# 4_esp8266.net
KiCad netlist of a schematic drawn in Altium Designer
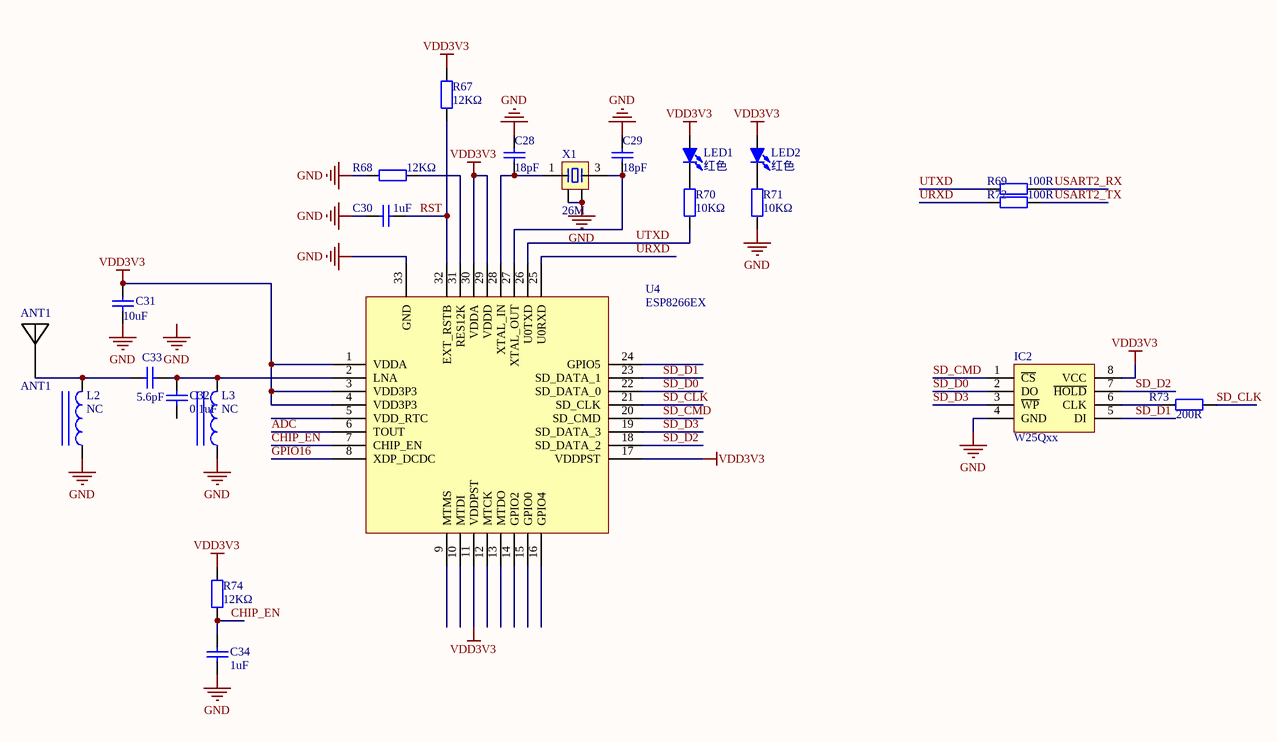
[diagram p0: 4_esp8266.SchDoc]

(export (version "E")
  (design (tool "Eeschema 10.0.6"))
  (components
    (comp (ref "ANT1")
      (value "ANT1")
      (footprint "WIFI-ANT")
      (description "PCB板载天线")
      (fields (field (name "版权归属") "源创客"))
      (libsource (lib "14.1 - 天线") (part "ANT1"))
    )
    (comp (ref "C28")
      (value "18pF")
      (footprint "LC-0603_C")
      (description "贴片电容")
      (libsource (lib "Miscellaneous Devices LC") (part "0603 1nF (102) 10% 50V"))
    )
    (comp (ref "C29")
      (value "18pF")
      (footprint "LC-0603_C")
      (description "贴片电容")
      (libsource (lib "Miscellaneous Devices LC") (part "0603 1nF (102) 10% 50V"))
    )
    (comp (ref "C30")
      (value "1uF")
      (footprint "LC-0603_C")
      (description "贴片电容")
      (libsource (lib "Miscellaneous Devices LC") (part "0603 1nF (102) 10% 50V"))
    )
    (comp (ref "C31")
      (value "10uF")
      (footprint "LC-0805_C")
      (description "贴片电容")
      (libsource (lib "Miscellaneous Devices LC") (part "0805 33pF (330) 5% 50V"))
    )
    (comp (ref "C32")
      (value "0.1uF")
      (footprint "LC-0603_C")
      (description "贴片电容")
      (libsource (lib "Miscellaneous Devices LC") (part "0603 1nF (102) 10% 50V"))
    )
    (comp (ref "C33")
      (value "5.6pF")
      (footprint "LC-0603_C")
      (description "贴片电容")
      (libsource (lib "Miscellaneous Devices LC") (part "0603 1nF (102) 10% 50V"))
    )
    (comp (ref "C34")
      (value "1uF")
      (footprint "LC-0603_C")
      (description "贴片电容")
      (libsource (lib "Miscellaneous Devices LC") (part "0603 1nF (102) 10% 50V"))
    )
    (comp (ref "IC2")
      (value "W25Qxx")
      (footprint "SOP8W_M")
      (description "外置Flash")
      (fields (field (name "版权归属") "源创客"))
      (libsource (lib "1.1   - IC芯片") (part "W25Qxx"))
    )
    (comp (ref "L2")
      (value "NC")
      (footprint "LC-0603_L")
      (description "贴片电感")
      (libsource (lib "Miscellaneous Devices LC") (part "0603 10uH 10%"))
    )
    (comp (ref "L3")
      (value "NC")
      (footprint "LC-0603_L")
      (description "贴片电感")
      (libsource (lib "Miscellaneous Devices LC") (part "0603 10uH 10%"))
    )
    (comp (ref "LED1")
      (value "红色")
      (footprint "LED 0603G")
      (description "贴片LED")
      (fields (field (name "版权归属") "源创客"))
      (libsource (lib "9.1   - LED") (part "LED-SMD"))
    )
    (comp (ref "LED2")
      (value "红色")
      (footprint "LED 0603G")
      (description "贴片LED")
      (fields (field (name "版权归属") "源创客"))
      (libsource (lib "9.1   - LED") (part "LED-SMD"))
    )
    (comp (ref "R67")
      (value "12KΩ")
      (footprint "LC-0603_R")
      (description "贴片电阻")
      (libsource (lib "Miscellaneous Devices LC") (part "0603 1.8KΩ (1801) 1%"))
    )
    (comp (ref "R68")
      (value "12KΩ")
      (footprint "LC-0603_R")
      (description "贴片电阻")
      (libsource (lib "") (part "0603 1.8KΩ (1801) 1%_1"))
    )
    (comp (ref "R69")
      (value "100R")
      (footprint "LC-0603_R")
      (description "贴片电阻")
      (fields (field (name "PUBLISHER") "Altium Limited"))
      (libsource (lib "liu_2016") (part "Res1"))
    )
    (comp (ref "R70")
      (value "10KΩ")
      (footprint "LC-0603_R")
      (description "贴片电阻")
      (libsource (lib "") (part "0603 1.8KΩ (1801) 1%_2"))
    )
    (comp (ref "R71")
      (value "10KΩ")
      (footprint "LC-0603_R")
      (description "贴片电阻")
      (libsource (lib "Miscellaneous Devices LC") (part "0603 1.8KΩ (1801) 1%"))
    )
    (comp (ref "R72")
      (value "100R")
      (footprint "LC-0603_R")
      (description "贴片电阻")
      (fields (field (name "PUBLISHER") "Altium Limited"))
      (libsource (lib "liu_2016") (part "Res1"))
    )
    (comp (ref "R73")
      (value "200R")
      (footprint "LC-0603_R")
      (description "贴片电阻")
      (libsource (lib "") (part "0603 1.8KΩ (1801) 1%_1"))
    )
    (comp (ref "R74")
      (value "12KΩ")
      (footprint "LC-0603_R")
      (description "贴片电阻")
      (libsource (lib "Miscellaneous Devices LC") (part "0603 1.8KΩ (1801) 1%"))
    )
    (comp (ref "U4")
      (value "ESP8266EX")
      (footprint "QFN32 5x5_M")
      (description "WIFI芯片")
      (libsource (lib "11.1 - 传感元件") (part "ESP8266EX"))
    )
    (comp (ref "X1")
      (value "26M")
      (footprint "OSC 2025-4P")
      (description "4脚无源晶振")
      (fields (field (name "版权归属") "源创客"))
      (libsource (lib "10.1 - 保险丝-晶振") (part "XTAL-4P"))
    )
  )
  (nets
    (net (code "1") (name "/ADC") (class "Default")
      (node (ref "U4") (pin "6") (pinfunction "TOUT_6") (pintype "passive"))
    )
    (net (code "2") (name "/CHIP_EN") (class "Default")
      (node (ref "C34") (pin "1") (pinfunction "1_1") (pintype "passive"))
      (node (ref "R74") (pin "1") (pinfunction "1_1") (pintype "passive"))
      (node (ref "U4") (pin "7") (pinfunction "CHIP_EN_7") (pintype "passive"))
    )
    (net (code "3") (name "/GPIO16") (class "Default")
      (node (ref "U4") (pin "8") (pinfunction "XDP_DCDC_8") (pintype "passive"))
    )
    (net (code "4") (name "/RST") (class "Default")
      (node (ref "C30") (pin "1") (pinfunction "1_1") (pintype "passive"))
      (node (ref "R67") (pin "1") (pinfunction "1_1") (pintype "passive"))
      (node (ref "U4") (pin "32") (pinfunction "EXT_RSTB_32") (pintype "passive"))
    )
    (net (code "5") (name "/SD_CLK") (class "Default")
      (node (ref "R73") (pin "1") (pinfunction "1_1") (pintype "passive"))
      (node (ref "U4") (pin "21") (pinfunction "SD_CLK_21") (pintype "passive"))
    )
    (net (code "6") (name "/SD_CMD") (class "Default")
      (node (ref "IC2") (pin "1") (pinfunction "~{CS}_1") (pintype "passive"))
      (node (ref "U4") (pin "20") (pinfunction "SD_CMD_20") (pintype "passive"))
    )
    (net (code "7") (name "/SD_D0") (class "Default")
      (node (ref "IC2") (pin "2") (pinfunction "DO_2") (pintype "passive"))
      (node (ref "U4") (pin "22") (pinfunction "SD_DATA_0_22") (pintype "passive"))
    )
    (net (code "8") (name "/SD_D1") (class "Default")
      (node (ref "IC2") (pin "5") (pinfunction "DI_5") (pintype "passive"))
      (node (ref "U4") (pin "23") (pinfunction "SD_DATA_1_23") (pintype "passive"))
    )
    (net (code "9") (name "/SD_D2") (class "Default")
      (node (ref "IC2") (pin "7") (pinfunction "~{HOLD}_7") (pintype "passive"))
      (node (ref "U4") (pin "18") (pinfunction "SD_DATA_2_18") (pintype "passive"))
    )
    (net (code "10") (name "/SD_D3") (class "Default")
      (node (ref "IC2") (pin "3") (pinfunction "~{WP}_3") (pintype "passive"))
      (node (ref "U4") (pin "19") (pinfunction "SD_DATA_3_19") (pintype "passive"))
    )
    (net (code "11") (name "/URXD") (class "Default")
      (node (ref "R72") (pin "2") (pinfunction "2_2") (pintype "passive"))
      (node (ref "U4") (pin "25") (pinfunction "U0RXD_25") (pintype "passive"))
    )
    (net (code "12") (name "/USART2_RX") (class "Default")
      (node (ref "R69") (pin "1") (pinfunction "1_1") (pintype "passive"))
    )
    (net (code "13") (name "/USART2_TX") (class "Default")
      (node (ref "R72") (pin "1") (pinfunction "1_1") (pintype "passive"))
    )
    (net (code "14") (name "/UTXD") (class "Default")
      (node (ref "R69") (pin "2") (pinfunction "2_2") (pintype "passive"))
      (node (ref "R70") (pin "2") (pinfunction "2_2") (pintype "passive"))
      (node (ref "U4") (pin "26") (pinfunction "U0TXD_26") (pintype "passive"))
    )
    (net (code "15") (name "GND") (class "Default")
      (node (ref "C28") (pin "1") (pinfunction "1_1") (pintype "passive"))
      (node (ref "C29") (pin "1") (pinfunction "1_1") (pintype "passive"))
      (node (ref "C30") (pin "2") (pinfunction "2_2") (pintype "passive"))
      (node (ref "C31") (pin "1") (pinfunction "1_1") (pintype "passive"))
      (node (ref "C34") (pin "2") (pinfunction "2_2") (pintype "passive"))
      (node (ref "IC2") (pin "4") (pinfunction "GND_4") (pintype "passive"))
      (node (ref "L2") (pin "1") (pinfunction "1_1") (pintype "passive"))
      (node (ref "L3") (pin "1") (pinfunction "1_1") (pintype "passive"))
      (node (ref "R68") (pin "2") (pinfunction "2_2") (pintype "passive"))
      (node (ref "R71") (pin "1") (pinfunction "1_1") (pintype "passive"))
      (node (ref "U4") (pin "33") (pinfunction "GND_33") (pintype "passive"))
      (node (ref "X1") (pin "2") (pinfunction "2_2") (pintype "passive"))
      (node (ref "X1") (pin "4") (pinfunction "4_4") (pintype "passive"))
    )
    (net (code "16") (name "Net-(ANT1-Pad1)") (class "Default")
      (node (ref "ANT1") (pin "1") (pinfunction "1_1") (pintype "passive"))
      (node (ref "C33") (pin "1") (pinfunction "1_1") (pintype "passive"))
      (node (ref "L2") (pin "2") (pinfunction "2_2") (pintype "passive"))
    )
    (net (code "17") (name "Net-(IC2-CLK)") (class "Default")
      (node (ref "IC2") (pin "6") (pinfunction "CLK_6") (pintype "passive"))
      (node (ref "R73") (pin "2") (pinfunction "2_2") (pintype "passive"))
    )
    (net (code "18") (name "Net-(LED1-K)") (class "Default")
      (node (ref "LED1") (pin "2") (pinfunction "K_2") (pintype "passive"))
      (node (ref "R70") (pin "1") (pinfunction "1_1") (pintype "passive"))
    )
    (net (code "19") (name "Net-(LED2-K)") (class "Default")
      (node (ref "LED2") (pin "2") (pinfunction "K_2") (pintype "passive"))
      (node (ref "R71") (pin "2") (pinfunction "2_2") (pintype "passive"))
    )
    (net (code "20") (name "Net-(U4-LNA)") (class "Default")
      (node (ref "C32") (pin "1") (pinfunction "1_1") (pintype "passive"))
      (node (ref "C33") (pin "2") (pinfunction "2_2") (pintype "passive"))
      (node (ref "L3") (pin "2") (pinfunction "2_2") (pintype "passive"))
      (node (ref "U4") (pin "2") (pinfunction "LNA_2") (pintype "passive"))
    )
    (net (code "21") (name "Net-(U4-RES12K)") (class "Default")
      (node (ref "R68") (pin "1") (pinfunction "1_1") (pintype "passive"))
      (node (ref "U4") (pin "31") (pinfunction "RES12K_31") (pintype "passive"))
    )
    (net (code "22") (name "Net-(U4-XTAL_IN)") (class "Default")
      (node (ref "C28") (pin "2") (pinfunction "2_2") (pintype "passive"))
      (node (ref "U4") (pin "28") (pinfunction "XTAL_IN_28") (pintype "passive"))
      (node (ref "X1") (pin "1") (pinfunction "1_1") (pintype "passive"))
    )
    (net (code "23") (name "Net-(U4-XTAL_OUT)") (class "Default")
      (node (ref "C29") (pin "2") (pinfunction "2_2") (pintype "passive"))
      (node (ref "U4") (pin "27") (pinfunction "XTAL_OUT_27") (pintype "passive"))
      (node (ref "X1") (pin "3") (pinfunction "3_3") (pintype "passive"))
    )
    (net (code "24") (name "VDD3V3") (class "Default")
      (node (ref "C31") (pin "2") (pinfunction "2_2") (pintype "passive"))
      (node (ref "IC2") (pin "8") (pinfunction "VCC_8") (pintype "passive"))
      (node (ref "LED1") (pin "1") (pinfunction "A_1") (pintype "passive"))
      (node (ref "LED2") (pin "1") (pinfunction "A_1") (pintype "passive"))
      (node (ref "R67") (pin "2") (pinfunction "2_2") (pintype "passive"))
      (node (ref "R74") (pin "2") (pinfunction "2_2") (pintype "passive"))
      (node (ref "U4") (pin "1") (pinfunction "VDDA_1") (pintype "passive"))
      (node (ref "U4") (pin "11") (pinfunction "VDDPST_11") (pintype "passive"))
      (node (ref "U4") (pin "17") (pinfunction "VDDPST_17") (pintype "passive"))
      (node (ref "U4") (pin "29") (pinfunction "VDDD_29") (pintype "passive"))
      (node (ref "U4") (pin "3") (pinfunction "VDD3P3_3") (pintype "passive"))
      (node (ref "U4") (pin "30") (pinfunction "VDDA_30") (pintype "passive"))
      (node (ref "U4") (pin "4") (pinfunction "VDD3P3_4") (pintype "passive"))
    )
    (net (code "25") (name "unconnected-(C32-Pad2)") (class "Default")
      (node (ref "C32") (pin "2") (pinfunction "2_2") (pintype "passive"))
    )
    (net (code "26") (name "unconnected-(U4-GPIO0-Pad15)") (class "Default")
      (node (ref "U4") (pin "15") (pinfunction "GPIO0_15") (pintype "passive"))
    )
    (net (code "27") (name "unconnected-(U4-GPIO2-Pad14)") (class "Default")
      (node (ref "U4") (pin "14") (pinfunction "GPIO2_14") (pintype "passive"))
    )
    (net (code "28") (name "unconnected-(U4-GPIO4-Pad16)") (class "Default")
      (node (ref "U4") (pin "16") (pinfunction "GPIO4_16") (pintype "passive"))
    )
    (net (code "29") (name "unconnected-(U4-GPIO5-Pad24)") (class "Default")
      (node (ref "U4") (pin "24") (pinfunction "GPIO5_24") (pintype "passive"))
    )
    (net (code "30") (name "unconnected-(U4-MTCK-Pad12)") (class "Default")
      (node (ref "U4") (pin "12") (pinfunction "MTCK_12") (pintype "passive"))
    )
    (net (code "31") (name "unconnected-(U4-MTDI-Pad10)") (class "Default")
      (node (ref "U4") (pin "10") (pinfunction "MTDI_10") (pintype "passive"))
    )
    (net (code "32") (name "unconnected-(U4-MTDO-Pad13)") (class "Default")
      (node (ref "U4") (pin "13") (pinfunction "MTDO_13") (pintype "passive"))
    )
    (net (code "33") (name "unconnected-(U4-MTMS-Pad9)") (class "Default")
      (node (ref "U4") (pin "9") (pinfunction "MTMS_9") (pintype "passive"))
    )
    (net (code "34") (name "unconnected-(U4-VDD_RTC-Pad5)") (class "Default")
      (node (ref "U4") (pin "5") (pinfunction "VDD_RTC_5") (pintype "passive"))
    )
  )
)
